# MCU.net
KiCad netlist of a schematic drawn in Altium Designer
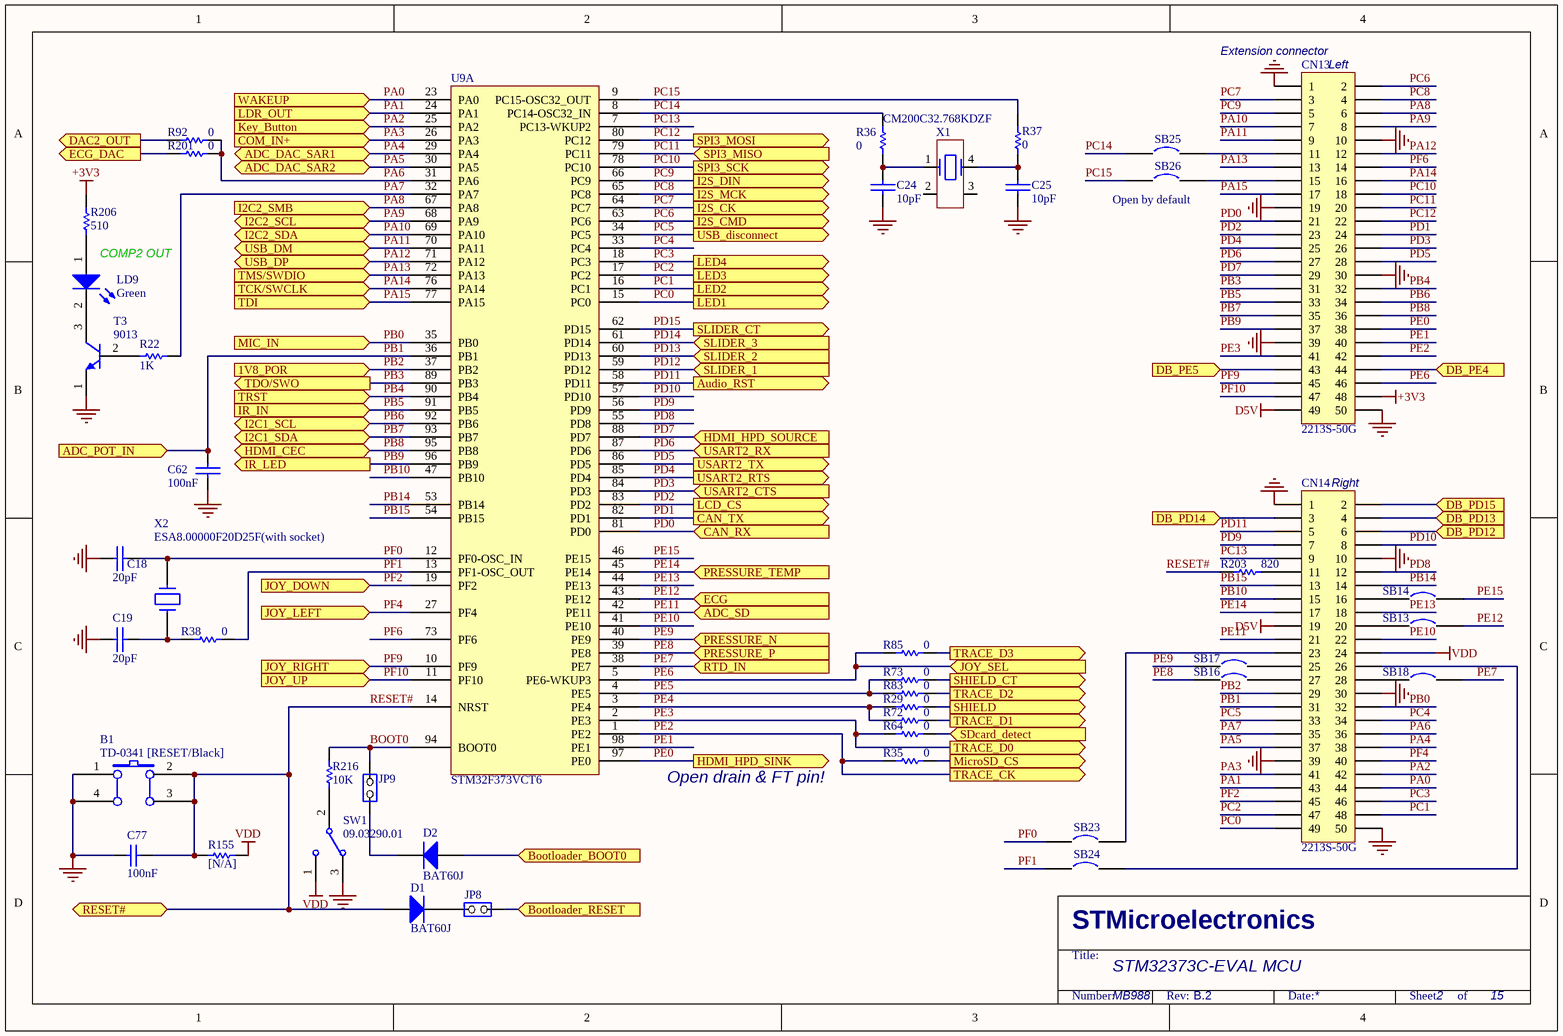
[diagram p0: MCU.SchDoc]

(export (version "E")
  (design (tool "Eeschema 10.0.6"))
  (components
    (comp (ref "B1")
      (value "TD-0341 [RESET/Black]")
      (footprint "PB10")
      (description "SE PUSHBUTTON")
      (libsource (lib "Documents") (part "SW PUSHBUTTON"))
    )
    (comp (ref "C18")
      (value "20pF")
      (footprint "0603C")
      (description "Capacitor")
      (libsource (lib "*") (part "CAP"))
    )
    (comp (ref "C19")
      (value "20pF")
      (footprint "0603C")
      (description "Capacitor")
      (libsource (lib "*") (part "CAP"))
    )
    (comp (ref "C24")
      (value "10pF")
      (footprint "0603C")
      (description "Capacitor")
      (libsource (lib "") (part "CAP_1"))
    )
    (comp (ref "C25")
      (value "10pF")
      (footprint "0603C")
      (description "Capacitor")
      (libsource (lib "") (part "CAP_1"))
    )
    (comp (ref "C62")
      (value "100nF")
      (footprint "0603C")
      (description "Capacitor")
      (libsource (lib "*") (part "CAP"))
    )
    (comp (ref "C77")
      (value "100nF")
      (footprint "0603C")
      (description "Capacitor")
      (fields (field (name "PUBLISHER") "Altium Limited"))
      (libsource (lib "Miscellaneous Devices") (part "CAP"))
    )
    (comp (ref "CN13")
      (value "2213S-50G")
      (footprint "2*25P")
      (description "Header, 25-Pin, Dual row")
      (fields (field (name "PUBLISHER") "Altium Limited"))
      (libsource (lib "Miscellaneous Connectors") (part "Header 25X2"))
    )
    (comp (ref "CN14")
      (value "2213S-50G")
      (footprint "2*25P")
      (description "Header, 25-Pin, Dual row")
      (fields (field (name "PUBLISHER") "Altium Limited"))
      (libsource (lib "Miscellaneous Connectors") (part "Header 25X2"))
    )
    (comp (ref "D1")
      (value "BAT60J")
      (footprint "SOD-323")
      (description "Default Diode")
      (fields (field (name "PUBLISHER") "Altium Limited"))
      (libsource (lib "Miscellaneous Devices") (part "Diode"))
    )
    (comp (ref "D2")
      (value "BAT60J")
      (footprint "SOD-323")
      (description "Default Diode")
      (fields (field (name "PUBLISHER") "Altium Limited"))
      (libsource (lib "Miscellaneous Devices") (part "Diode"))
    )
    (comp (ref "JP8") (value "~") (footprint "SIP2") (libsource (lib "*") (part "JP2")))
    (comp (ref "JP9") (value "~") (footprint "SIP2") (libsource (lib "*") (part "JP2")))
    (comp (ref "LD9")
      (value "Green")
      (footprint "0603D")
      (description "Typical RED, GREEN, YELLOW, AMBER GaAs LED")
      (fields (field (name "PUBLISHER") "Altium Limited"))
      (libsource (lib "Miscellaneous Devices") (part "LED2"))
    )
    (comp (ref "R22")
      (value "1K")
      (footprint "0603R")
      (description "Resistor")
      (fields (field (name "PUBLISHER") "Altium Limited"))
      (libsource (lib "Miscellaneous Devices") (part "Res1"))
    )
    (comp (ref "R29")
      (value "0")
      (footprint "0603R")
      (description "Resistor")
      (fields (field (name "PUBLISHER") "Altium Limited"))
      (libsource (lib "Miscellaneous Devices") (part "Res1"))
    )
    (comp (ref "R35")
      (value "0")
      (footprint "0603R")
      (description "Resistor")
      (fields (field (name "PUBLISHER") "Altium Limited"))
      (libsource (lib "Miscellaneous Devices") (part "Res1"))
    )
    (comp (ref "R36")
      (value "0")
      (footprint "0603R")
      (description "Resistor")
      (fields (field (name "PUBLISHER") "Altium Limited"))
      (libsource (lib "Miscellaneous Devices") (part "Res1"))
    )
    (comp (ref "R37")
      (value "0")
      (footprint "0603R")
      (description "Resistor")
      (fields (field (name "PUBLISHER") "Altium Limited"))
      (libsource (lib "Miscellaneous Devices") (part "Res1"))
    )
    (comp (ref "R38")
      (value "0")
      (footprint "0603R")
      (description "Resistor")
      (fields (field (name "PUBLISHER") "Altium Limited"))
      (libsource (lib "Miscellaneous Devices") (part "Res1"))
    )
    (comp (ref "R64")
      (value "0")
      (footprint "0603R")
      (description "Resistor")
      (fields (field (name "PUBLISHER") "Altium Limited"))
      (libsource (lib "Miscellaneous Devices") (part "Res1"))
    )
    (comp (ref "R72")
      (value "0")
      (footprint "0603R")
      (description "Resistor")
      (fields (field (name "PUBLISHER") "Altium Limited"))
      (libsource (lib "Miscellaneous Devices") (part "Res1"))
    )
    (comp (ref "R73")
      (value "0")
      (footprint "0603R")
      (description "Resistor")
      (fields (field (name "PUBLISHER") "Altium Limited"))
      (libsource (lib "Miscellaneous Devices") (part "Res1"))
    )
    (comp (ref "R83")
      (value "0")
      (footprint "0603R")
      (description "Resistor")
      (fields (field (name "PUBLISHER") "Altium Limited"))
      (libsource (lib "Miscellaneous Devices") (part "Res1"))
    )
    (comp (ref "R85")
      (value "0")
      (footprint "0603R")
      (description "Resistor")
      (fields (field (name "PUBLISHER") "Altium Limited"))
      (libsource (lib "Miscellaneous Devices") (part "Res1"))
    )
    (comp (ref "R92")
      (value "0")
      (footprint "0603R")
      (description "Resistor")
      (fields (field (name "PUBLISHER") "Altium Limited"))
      (libsource (lib "Miscellaneous Devices") (part "Res1"))
    )
    (comp (ref "R155")
      (value "[N/A]")
      (footprint "0603R")
      (description "Resistor")
      (fields (field (name "PUBLISHER") "Altium Limited"))
      (libsource (lib "Miscellaneous Devices") (part "res1"))
    )
    (comp (ref "R201")
      (value "0")
      (footprint "0603R")
      (description "Resistor")
      (fields (field (name "PUBLISHER") "Altium Limited"))
      (libsource (lib "Miscellaneous Devices") (part "Res1"))
    )
    (comp (ref "R203")
      (value "820")
      (footprint "0603R")
      (description "Resistor")
      (fields (field (name "PUBLISHER") "Altium Limited"))
      (libsource (lib "Miscellaneous Devices") (part "Res1"))
    )
    (comp (ref "R206")
      (value "510")
      (footprint "0603R")
      (description "Resistor")
      (fields (field (name "PUBLISHER") "Altium Limited"))
      (libsource (lib "Miscellaneous Devices") (part "Res1"))
    )
    (comp (ref "R216")
      (value "10K")
      (footprint "0603R")
      (description "Resistor")
      (fields (field (name "PUBLISHER") "Altium Limited"))
      (libsource (lib "Miscellaneous Devices") (part "res1"))
    )
    (comp (ref "SB13")
      (value "~")
      (footprint "JP2_SMD")
      (description "Circuit Breaker")
      (fields (field (name "PUBLISHER") "Altium Limited"))
      (libsource (lib "Miscellaneous Devices") (part "Circuit Breaker"))
    )
    (comp (ref "SB14")
      (value "~")
      (footprint "JP2_SMD")
      (description "Circuit Breaker")
      (fields (field (name "PUBLISHER") "Altium Limited"))
      (libsource (lib "Miscellaneous Devices") (part "Circuit Breaker"))
    )
    (comp (ref "SB16")
      (value "~")
      (footprint "JP2_SMD")
      (description "Circuit Breaker")
      (fields (field (name "PUBLISHER") "Altium Limited"))
      (libsource (lib "Miscellaneous Devices") (part "Circuit Breaker"))
    )
    (comp (ref "SB17")
      (value "~")
      (footprint "JP2_SMD")
      (description "Circuit Breaker")
      (fields (field (name "PUBLISHER") "Altium Limited"))
      (libsource (lib "Miscellaneous Devices") (part "Circuit Breaker"))
    )
    (comp (ref "SB18")
      (value "~")
      (footprint "JP2_SMD")
      (description "Circuit Breaker")
      (fields (field (name "PUBLISHER") "Altium Limited"))
      (libsource (lib "Miscellaneous Devices") (part "Circuit Breaker"))
    )
    (comp (ref "SB23")
      (value "~")
      (footprint "JP2_SMD")
      (description "Circuit Breaker")
      (fields (field (name "PUBLISHER") "Altium Limited"))
      (libsource (lib "Miscellaneous Devices") (part "Circuit Breaker"))
    )
    (comp (ref "SB24")
      (value "~")
      (footprint "JP2_SMD")
      (description "Circuit Breaker")
      (fields (field (name "PUBLISHER") "Altium Limited"))
      (libsource (lib "Miscellaneous Devices") (part "Circuit Breaker"))
    )
    (comp (ref "SB25")
      (value "~")
      (footprint "JP2_SMD")
      (description "Circuit Breaker")
      (fields (field (name "PUBLISHER") "Altium Limited"))
      (libsource (lib "Miscellaneous Devices") (part "Circuit Breaker"))
    )
    (comp (ref "SB26")
      (value "~")
      (footprint "JP2_SMD")
      (description "Circuit Breaker")
      (fields (field (name "PUBLISHER") "Altium Limited"))
      (libsource (lib "Miscellaneous Devices") (part "Circuit Breaker"))
    )
    (comp (ref "SW1")
      (value "09.03290.01")
      (footprint "SIP3")
      (description "SPDT Subminiature Toggle Switch, Right Angle Mounting, Vertical Actuation")
      (fields (field (name "PUBLISHER") "Altium Limited"))
      (libsource (lib "Miscellaneous Devices") (part "SW-SPDT"))
    )
    (comp (ref "T3")
      (value "9013")
      (footprint "SOT-23")
      (description "NPN Bipolar Transistor")
      (fields (field (name "PUBLISHER") "Altium Limited"))
      (libsource (lib "Miscellaneous Devices") (part "NPN"))
    )
    (comp (ref "U9")
      (value "STM32F373VCT6")
      (footprint "IC149-100-025-B5")
      (libsource (lib "MB988") (part "Goldfish"))
    )
    (comp (ref "X1") (value "CM200C32.768KDZF") (footprint "SM8") (libsource (lib "*") (part "MC306")))
    (comp (ref "X2")
      (value "ESA8.00000F20D25F(with socket)")
      (footprint "XTAL_socket")
      (description "Crystal")
      (libsource (lib "*") (part "CRYSTAL"))
    )
  )
  (nets
    (net (code "1") (name "+3V3") (class "Default")
      (node (ref "CN13") (pin "48") (pinfunction "48_48") (pintype "passive"))
      (node (ref "R206") (pin "1") (pinfunction "1_1") (pintype "passive"))
    )
    (net (code "2") (name "/BOOT0") (class "Default")
      (node (ref "JP9") (pin "2") (pinfunction "NO_2") (pintype "passive"))
      (node (ref "R216") (pin "1") (pinfunction "1_1") (pintype "passive"))
      (node (ref "U9") (pin "94") (pinfunction "BOOT0_94") (pintype "passive"))
    )
    (net (code "3") (name "/Bootloader_BOOT0") (class "Default")
      (node (ref "D2") (pin "1") (pinfunction "A_1") (pintype "passive"))
    )
    (net (code "4") (name "/Bootloader_RESET") (class "Default")
      (node (ref "JP8") (pin "2") (pinfunction "NO_2") (pintype "passive"))
    )
    (net (code "5") (name "/DAC2_OUT") (class "Default")
      (node (ref "R92") (pin "2") (pinfunction "2_2") (pintype "passive"))
    )
    (net (code "6") (name "/DB_PD12") (class "Default")
      (node (ref "CN14") (pin "6") (pinfunction "6_6") (pintype "passive"))
    )
    (net (code "7") (name "/DB_PD13") (class "Default")
      (node (ref "CN14") (pin "4") (pinfunction "4_4") (pintype "passive"))
    )
    (net (code "8") (name "/DB_PD14") (class "Default")
      (node (ref "CN14") (pin "3") (pinfunction "3_3") (pintype "passive"))
    )
    (net (code "9") (name "/DB_PD15") (class "Default")
      (node (ref "CN14") (pin "2") (pinfunction "2_2") (pintype "passive"))
    )
    (net (code "10") (name "/DB_PE4") (class "Default")
      (node (ref "CN13") (pin "44") (pinfunction "44_44") (pintype "passive"))
    )
    (net (code "11") (name "/DB_PE5") (class "Default")
      (node (ref "CN13") (pin "43") (pinfunction "43_43") (pintype "passive"))
    )
    (net (code "12") (name "/ECG_DAC") (class "Default")
      (node (ref "R201") (pin "2") (pinfunction "2_2") (pintype "passive"))
    )
    (net (code "13") (name "/MicroSD_CS") (class "Default")
      (node (ref "R35") (pin "1") (pinfunction "1_1") (pintype "passive"))
    )
    (net (code "14") (name "/PA0") (class "Default")
      (node (ref "CN14") (pin "44") (pinfunction "44_44") (pintype "passive"))
      (node (ref "U9") (pin "23") (pinfunction "PA0_23") (pintype "passive"))
    )
    (net (code "15") (name "/PA1") (class "Default")
      (node (ref "CN14") (pin "43") (pinfunction "43_43") (pintype "passive"))
      (node (ref "U9") (pin "24") (pinfunction "PA1_24") (pintype "passive"))
    )
    (net (code "16") (name "/PA2") (class "Default")
      (node (ref "CN14") (pin "42") (pinfunction "42_42") (pintype "passive"))
      (node (ref "U9") (pin "25") (pinfunction "PA2_25") (pintype "passive"))
    )
    (net (code "17") (name "/PA3") (class "Default")
      (node (ref "CN14") (pin "41") (pinfunction "41_41") (pintype "passive"))
      (node (ref "U9") (pin "26") (pinfunction "PA3_26") (pintype "passive"))
    )
    (net (code "18") (name "/PA4") (class "Default")
      (node (ref "CN14") (pin "38") (pinfunction "38_38") (pintype "passive"))
      (node (ref "U9") (pin "29") (pinfunction "PA4_29") (pintype "passive"))
    )
    (net (code "19") (name "/PA5") (class "Default")
      (node (ref "CN14") (pin "37") (pinfunction "37_37") (pintype "passive"))
      (node (ref "U9") (pin "30") (pinfunction "PA5_30") (pintype "passive"))
    )
    (net (code "20") (name "/PA6") (class "Default")
      (node (ref "CN14") (pin "36") (pinfunction "36_36") (pintype "passive"))
      (node (ref "R201") (pin "1") (pinfunction "1_1") (pintype "passive"))
      (node (ref "R92") (pin "1") (pinfunction "1_1") (pintype "passive"))
      (node (ref "U9") (pin "31") (pinfunction "PA6_31") (pintype "passive"))
    )
    (net (code "21") (name "/PA7") (class "Default")
      (node (ref "CN14") (pin "35") (pinfunction "35_35") (pintype "passive"))
      (node (ref "R22") (pin "2") (pinfunction "2_2") (pintype "passive"))
      (node (ref "U9") (pin "32") (pinfunction "PA7_32") (pintype "passive"))
    )
    (net (code "22") (name "/PA8") (class "Default")
      (node (ref "CN13") (pin "6") (pinfunction "6_6") (pintype "passive"))
      (node (ref "U9") (pin "67") (pinfunction "PA8_67") (pintype "passive"))
    )
    (net (code "23") (name "/PA9") (class "Default")
      (node (ref "CN13") (pin "8") (pinfunction "8_8") (pintype "passive"))
      (node (ref "U9") (pin "68") (pinfunction "PA9_68") (pintype "passive"))
    )
    (net (code "24") (name "/PA10") (class "Default")
      (node (ref "CN13") (pin "7") (pinfunction "7_7") (pintype "passive"))
      (node (ref "U9") (pin "69") (pinfunction "PA10_69") (pintype "passive"))
    )
    (net (code "25") (name "/PA11") (class "Default")
      (node (ref "CN13") (pin "9") (pinfunction "9_9") (pintype "passive"))
      (node (ref "U9") (pin "70") (pinfunction "PA11_70") (pintype "passive"))
    )
    (net (code "26") (name "/PA12") (class "Default")
      (node (ref "CN13") (pin "12") (pinfunction "12_12") (pintype "passive"))
      (node (ref "U9") (pin "71") (pinfunction "PA12_71") (pintype "passive"))
    )
    (net (code "27") (name "/PA13") (class "Default")
      (node (ref "CN13") (pin "13") (pinfunction "13_13") (pintype "passive"))
      (node (ref "U9") (pin "72") (pinfunction "PA13_72") (pintype "passive"))
    )
    (net (code "28") (name "/PA14") (class "Default")
      (node (ref "CN13") (pin "16") (pinfunction "16_16") (pintype "passive"))
      (node (ref "U9") (pin "76") (pinfunction "PA14_76") (pintype "passive"))
    )
    (net (code "29") (name "/PA15") (class "Default")
      (node (ref "CN13") (pin "17") (pinfunction "17_17") (pintype "passive"))
      (node (ref "U9") (pin "77") (pinfunction "PA15_77") (pintype "passive"))
    )
    (net (code "30") (name "/PB0") (class "Default")
      (node (ref "CN14") (pin "32") (pinfunction "32_32") (pintype "passive"))
      (node (ref "U9") (pin "35") (pinfunction "PB0_35") (pintype "passive"))
    )
    (net (code "31") (name "/PB1") (class "Default")
      (node (ref "C62") (pin "2") (pinfunction "2_2") (pintype "passive"))
      (node (ref "CN14") (pin "31") (pinfunction "31_31") (pintype "passive"))
      (node (ref "U9") (pin "36") (pinfunction "PB1_36") (pintype "passive"))
    )
    (net (code "32") (name "/PB2") (class "Default")
      (node (ref "CN14") (pin "29") (pinfunction "29_29") (pintype "passive"))
      (node (ref "U9") (pin "37") (pinfunction "PB2_37") (pintype "passive"))
    )
    (net (code "33") (name "/PB3") (class "Default")
      (node (ref "CN13") (pin "31") (pinfunction "31_31") (pintype "passive"))
      (node (ref "U9") (pin "89") (pinfunction "PB3_89") (pintype "passive"))
    )
    (net (code "34") (name "/PB4") (class "Default")
      (node (ref "CN13") (pin "32") (pinfunction "32_32") (pintype "passive"))
      (node (ref "U9") (pin "90") (pinfunction "PB4_90") (pintype "passive"))
    )
    (net (code "35") (name "/PB5") (class "Default")
      (node (ref "CN13") (pin "33") (pinfunction "33_33") (pintype "passive"))
      (node (ref "U9") (pin "91") (pinfunction "PB5_91") (pintype "passive"))
    )
    (net (code "36") (name "/PB6") (class "Default")
      (node (ref "CN13") (pin "34") (pinfunction "34_34") (pintype "passive"))
      (node (ref "U9") (pin "92") (pinfunction "PB6_92") (pintype "passive"))
    )
    (net (code "37") (name "/PB7") (class "Default")
      (node (ref "CN13") (pin "35") (pinfunction "35_35") (pintype "passive"))
      (node (ref "U9") (pin "93") (pinfunction "PB7_93") (pintype "passive"))
    )
    (net (code "38") (name "/PB8") (class "Default")
      (node (ref "CN13") (pin "36") (pinfunction "36_36") (pintype "passive"))
      (node (ref "U9") (pin "95") (pinfunction "PB8_95") (pintype "passive"))
    )
    (net (code "39") (name "/PB9") (class "Default")
      (node (ref "CN13") (pin "37") (pinfunction "37_37") (pintype "passive"))
      (node (ref "U9") (pin "96") (pinfunction "PB9_96") (pintype "passive"))
    )
    (net (code "40") (name "/PB10") (class "Default")
      (node (ref "CN14") (pin "15") (pinfunction "15_15") (pintype "passive"))
      (node (ref "U9") (pin "47") (pinfunction "PB10_47") (pintype "passive"))
    )
    (net (code "41") (name "/PB14") (class "Default")
      (node (ref "CN14") (pin "14") (pinfunction "14_14") (pintype "passive"))
      (node (ref "U9") (pin "53") (pinfunction "PB14_53") (pintype "passive"))
    )
    (net (code "42") (name "/PB15") (class "Default")
      (node (ref "CN14") (pin "13") (pinfunction "13_13") (pintype "passive"))
      (node (ref "U9") (pin "54") (pinfunction "PB15_54") (pintype "passive"))
    )
    (net (code "43") (name "/PC0") (class "Default")
      (node (ref "CN14") (pin "49") (pinfunction "49_49") (pintype "passive"))
      (node (ref "U9") (pin "15") (pinfunction "PC0_15") (pintype "passive"))
    )
    (net (code "44") (name "/PC1") (class "Default")
      (node (ref "CN14") (pin "48") (pinfunction "48_48") (pintype "passive"))
      (node (ref "U9") (pin "16") (pinfunction "PC1_16") (pintype "passive"))
    )
    (net (code "45") (name "/PC2") (class "Default")
      (node (ref "CN14") (pin "47") (pinfunction "47_47") (pintype "passive"))
      (node (ref "U9") (pin "17") (pinfunction "PC2_17") (pintype "passive"))
    )
    (net (code "46") (name "/PC3") (class "Default")
      (node (ref "CN14") (pin "46") (pinfunction "46_46") (pintype "passive"))
      (node (ref "U9") (pin "18") (pinfunction "PC3_18") (pintype "passive"))
    )
    (net (code "47") (name "/PC4") (class "Default")
      (node (ref "CN14") (pin "34") (pinfunction "34_34") (pintype "passive"))
      (node (ref "U9") (pin "33") (pinfunction "PC4_33") (pintype "passive"))
    )
    (net (code "48") (name "/PC5") (class "Default")
      (node (ref "CN14") (pin "33") (pinfunction "33_33") (pintype "passive"))
      (node (ref "U9") (pin "34") (pinfunction "PC5_34") (pintype "passive"))
    )
    (net (code "49") (name "/PC6") (class "Default")
      (node (ref "CN13") (pin "2") (pinfunction "2_2") (pintype "passive"))
      (node (ref "U9") (pin "63") (pinfunction "PC6_63") (pintype "passive"))
    )
    (net (code "50") (name "/PC7") (class "Default")
      (node (ref "CN13") (pin "3") (pinfunction "3_3") (pintype "passive"))
      (node (ref "U9") (pin "64") (pinfunction "PC7_64") (pintype "passive"))
    )
    (net (code "51") (name "/PC8") (class "Default")
      (node (ref "CN13") (pin "4") (pinfunction "4_4") (pintype "passive"))
      (node (ref "U9") (pin "65") (pinfunction "PC8_65") (pintype "passive"))
    )
    (net (code "52") (name "/PC9") (class "Default")
      (node (ref "CN13") (pin "5") (pinfunction "5_5") (pintype "passive"))
      (node (ref "U9") (pin "66") (pinfunction "PC9_66") (pintype "passive"))
    )
    (net (code "53") (name "/PC10") (class "Default")
      (node (ref "CN13") (pin "18") (pinfunction "18_18") (pintype "passive"))
      (node (ref "U9") (pin "78") (pinfunction "PC10_78") (pintype "passive"))
    )
    (net (code "54") (name "/PC11") (class "Default")
      (node (ref "CN13") (pin "20") (pinfunction "20_20") (pintype "passive"))
      (node (ref "U9") (pin "79") (pinfunction "PC11_79") (pintype "passive"))
    )
    (net (code "55") (name "/PC12") (class "Default")
      (node (ref "CN13") (pin "22") (pinfunction "22_22") (pintype "passive"))
      (node (ref "U9") (pin "80") (pinfunction "PC12_80") (pintype "passive"))
    )
    (net (code "56") (name "/PC13") (class "Default")
      (node (ref "CN14") (pin "9") (pinfunction "9_9") (pintype "passive"))
      (node (ref "U9") (pin "7") (pinfunction "PC13-WKUP2_7") (pintype "passive"))
    )
    (net (code "57") (name "/PC14") (class "Default")
      (node (ref "R36") (pin "2") (pinfunction "2_2") (pintype "passive"))
      (node (ref "SB25") (pin "1") (pinfunction "1_1") (pintype "passive"))
      (node (ref "U9") (pin "8") (pinfunction "PC14-OSC32_IN_8") (pintype "passive"))
    )
    (net (code "58") (name "/PC15") (class "Default")
      (node (ref "R37") (pin "2") (pinfunction "2_2") (pintype "passive"))
      (node (ref "SB26") (pin "1") (pinfunction "1_1") (pintype "passive"))
      (node (ref "U9") (pin "9") (pinfunction "PC15-OSC32_OUT_9") (pintype "passive"))
    )
    (net (code "59") (name "/PD0") (class "Default")
      (node (ref "CN13") (pin "21") (pinfunction "21_21") (pintype "passive"))
      (node (ref "U9") (pin "81") (pinfunction "PD0_81") (pintype "passive"))
    )
    (net (code "60") (name "/PD1") (class "Default")
      (node (ref "CN13") (pin "24") (pinfunction "24_24") (pintype "passive"))
      (node (ref "U9") (pin "82") (pinfunction "PD1_82") (pintype "passive"))
    )
    (net (code "61") (name "/PD2") (class "Default")
      (node (ref "CN13") (pin "23") (pinfunction "23_23") (pintype "passive"))
      (node (ref "U9") (pin "83") (pinfunction "PD2_83") (pintype "passive"))
    )
    (net (code "62") (name "/PD3") (class "Default")
      (node (ref "CN13") (pin "26") (pinfunction "26_26") (pintype "passive"))
      (node (ref "U9") (pin "84") (pinfunction "PD3_84") (pintype "passive"))
    )
    (net (code "63") (name "/PD4") (class "Default")
      (node (ref "CN13") (pin "25") (pinfunction "25_25") (pintype "passive"))
      (node (ref "U9") (pin "85") (pinfunction "PD4_85") (pintype "passive"))
    )
    (net (code "64") (name "/PD5") (class "Default")
      (node (ref "CN13") (pin "28") (pinfunction "28_28") (pintype "passive"))
      (node (ref "U9") (pin "86") (pinfunction "PD5_86") (pintype "passive"))
    )
    (net (code "65") (name "/PD6") (class "Default")
      (node (ref "CN13") (pin "27") (pinfunction "27_27") (pintype "passive"))
      (node (ref "U9") (pin "87") (pinfunction "PD6_87") (pintype "passive"))
    )
    (net (code "66") (name "/PD7") (class "Default")
      (node (ref "CN13") (pin "29") (pinfunction "29_29") (pintype "passive"))
      (node (ref "U9") (pin "88") (pinfunction "PD7_88") (pintype "passive"))
    )
    (net (code "67") (name "/PD8") (class "Default")
      (node (ref "CN14") (pin "12") (pinfunction "12_12") (pintype "passive"))
      (node (ref "U9") (pin "55") (pinfunction "PD8_55") (pintype "passive"))
    )
    (net (code "68") (name "/PD9") (class "Default")
      (node (ref "CN14") (pin "7") (pinfunction "7_7") (pintype "passive"))
      (node (ref "U9") (pin "56") (pinfunction "PD9_56") (pintype "passive"))
    )
    (net (code "69") (name "/PD10") (class "Default")
      (node (ref "CN14") (pin "8") (pinfunction "8_8") (pintype "passive"))
      (node (ref "U9") (pin "57") (pinfunction "PD10_57") (pintype "passive"))
    )
    (net (code "70") (name "/PD11") (class "Default")
      (node (ref "CN14") (pin "5") (pinfunction "5_5") (pintype "passive"))
      (node (ref "U9") (pin "58") (pinfunction "PD11_58") (pintype "passive"))
    )
    (net (code "71") (name "/PD12") (class "Default")
      (node (ref "U9") (pin "59") (pinfunction "PD12_59") (pintype "passive"))
    )
    (net (code "72") (name "/PD13") (class "Default")
      (node (ref "U9") (pin "60") (pinfunction "PD13_60") (pintype "passive"))
    )
    (net (code "73") (name "/PD14") (class "Default")
      (node (ref "U9") (pin "61") (pinfunction "PD14_61") (pintype "passive"))
    )
    (net (code "74") (name "/PD15") (class "Default")
      (node (ref "U9") (pin "62") (pinfunction "PD15_62") (pintype "passive"))
    )
    (net (code "75") (name "/PE0") (class "Default")
      (node (ref "CN13") (pin "38") (pinfunction "38_38") (pintype "passive"))
      (node (ref "U9") (pin "97") (pinfunction "PE0_97") (pintype "passive"))
    )
    (net (code "76") (name "/PE1") (class "Default")
      (node (ref "CN13") (pin "40") (pinfunction "40_40") (pintype "passive"))
      (node (ref "U9") (pin "98") (pinfunction "PE1_98") (pintype "passive"))
    )
    (net (code "77") (name "/PE2") (class "Default")
      (node (ref "CN13") (pin "42") (pinfunction "42_42") (pintype "passive"))
      (node (ref "R35") (pin "2") (pinfunction "2_2") (pintype "passive"))
      (node (ref "U9") (pin "1") (pinfunction "PE2_1") (pintype "passive"))
    )
    (net (code "78") (name "/PE3") (class "Default")
      (node (ref "CN13") (pin "41") (pinfunction "41_41") (pintype "passive"))
      (node (ref "R64") (pin "2") (pinfunction "2_2") (pintype "passive"))
      (node (ref "U9") (pin "2") (pinfunction "PE3_2") (pintype "passive"))
    )
    (net (code "79") (name "/PE4") (class "Default")
      (node (ref "R29") (pin "2") (pinfunction "2_2") (pintype "passive"))
      (node (ref "R72") (pin "2") (pinfunction "2_2") (pintype "passive"))
      (node (ref "U9") (pin "3") (pinfunction "PE4_3") (pintype "passive"))
    )
    (net (code "80") (name "/PE5") (class "Default")
      (node (ref "R73") (pin "2") (pinfunction "2_2") (pintype "passive"))
      (node (ref "R83") (pin "2") (pinfunction "2_2") (pintype "passive"))
      (node (ref "U9") (pin "4") (pinfunction "PE5_4") (pintype "passive"))
    )
    (net (code "81") (name "/PE6") (class "Default")
      (node (ref "CN13") (pin "46") (pinfunction "46_46") (pintype "passive"))
      (node (ref "R85") (pin "2") (pinfunction "2_2") (pintype "passive"))
      (node (ref "U9") (pin "5") (pinfunction "PE6-WKUP3_5") (pintype "passive"))
    )
    (net (code "82") (name "/PE7") (class "Default")
      (node (ref "SB18") (pin "2") (pinfunction "2_2") (pintype "passive"))
      (node (ref "U9") (pin "38") (pinfunction "PE7_38") (pintype "passive"))
    )
    (net (code "83") (name "/PE8") (class "Default")
      (node (ref "SB16") (pin "1") (pinfunction "1_1") (pintype "passive"))
      (node (ref "U9") (pin "39") (pinfunction "PE8_39") (pintype "passive"))
    )
    (net (code "84") (name "/PE9") (class "Default")
      (node (ref "SB17") (pin "1") (pinfunction "1_1") (pintype "passive"))
      (node (ref "U9") (pin "40") (pinfunction "PE9_40") (pintype "passive"))
    )
    (net (code "85") (name "/PE10") (class "Default")
      (node (ref "CN14") (pin "22") (pinfunction "22_22") (pintype "passive"))
      (node (ref "U9") (pin "41") (pinfunction "PE10_41") (pintype "passive"))
    )
    (net (code "86") (name "/PE11") (class "Default")
      (node (ref "CN14") (pin "21") (pinfunction "21_21") (pintype "passive"))
      (node (ref "U9") (pin "42") (pinfunction "PE11_42") (pintype "passive"))
    )
    (net (code "87") (name "/PE12") (class "Default")
      (node (ref "SB13") (pin "2") (pinfunction "2_2") (pintype "passive"))
      (node (ref "U9") (pin "43") (pinfunction "PE12_43") (pintype "passive"))
    )
    (net (code "88") (name "/PE13") (class "Default")
      (node (ref "CN14") (pin "18") (pinfunction "18_18") (pintype "passive"))
      (node (ref "U9") (pin "44") (pinfunction "PE13_44") (pintype "passive"))
    )
    (net (code "89") (name "/PE14") (class "Default")
      (node (ref "CN14") (pin "17") (pinfunction "17_17") (pintype "passive"))
      (node (ref "U9") (pin "45") (pinfunction "PE14_45") (pintype "passive"))
    )
    (net (code "90") (name "/PE15") (class "Default")
      (node (ref "SB14") (pin "2") (pinfunction "2_2") (pintype "passive"))
      (node (ref "U9") (pin "46") (pinfunction "PE15_46") (pintype "passive"))
    )
    (net (code "91") (name "/PF0") (class "Default")
      (node (ref "C18") (pin "1") (pinfunction "1_1") (pintype "passive"))
      (node (ref "SB23") (pin "1") (pinfunction "1_1") (pintype "passive"))
      (node (ref "U9") (pin "12") (pinfunction "PF0-OSC_IN_12") (pintype "passive"))
      (node (ref "X2") (pin "2") (pinfunction "2_2") (pintype "passive"))
    )
    (net (code "92") (name "/PF1") (class "Default")
      (node (ref "R38") (pin "1") (pinfunction "1_1") (pintype "passive"))
      (node (ref "SB24") (pin "1") (pinfunction "1_1") (pintype "passive"))
      (node (ref "U9") (pin "13") (pinfunction "PF1-OSC_OUT_13") (pintype "passive"))
    )
    (net (code "93") (name "/PF2") (class "Default")
      (node (ref "CN14") (pin "45") (pinfunction "45_45") (pintype "passive"))
      (node (ref "U9") (pin "19") (pinfunction "PF2_19") (pintype "passive"))
    )
    (net (code "94") (name "/PF4") (class "Default")
      (node (ref "CN14") (pin "40") (pinfunction "40_40") (pintype "passive"))
      (node (ref "U9") (pin "27") (pinfunction "PF4_27") (pintype "passive"))
    )
    (net (code "95") (name "/PF6") (class "Default")
      (node (ref "CN13") (pin "14") (pinfunction "14_14") (pintype "passive"))
      (node (ref "U9") (pin "73") (pinfunction "PF6_73") (pintype "passive"))
    )
    (net (code "96") (name "/PF9") (class "Default")
      (node (ref "CN13") (pin "45") (pinfunction "45_45") (pintype "passive"))
      (node (ref "U9") (pin "10") (pinfunction "PF9_10") (pintype "passive"))
    )
    (net (code "97") (name "/PF10") (class "Default")
      (node (ref "CN13") (pin "47") (pinfunction "47_47") (pintype "passive"))
      (node (ref "U9") (pin "11") (pinfunction "PF10_11") (pintype "passive"))
    )
    (net (code "98") (name "/RESET#") (class "Default")
      (node (ref "B1") (pin "2") (pinfunction "B0_2") (pintype "passive"))
      (node (ref "B1") (pin "3") (pinfunction "B1_3") (pintype "passive"))
      (node (ref "C77") (pin "2") (pinfunction "2_2") (pintype "passive"))
      (node (ref "D1") (pin "1") (pinfunction "A_1") (pintype "passive"))
      (node (ref "R155") (pin "1") (pinfunction "1_1") (pintype "passive"))
      (node (ref "R203") (pin "2") (pinfunction "2_2") (pintype "passive"))
      (node (ref "U9") (pin "14") (pinfunction "NRST_14") (pintype "passive"))
    )
    (net (code "99") (name "/SDcard_detect") (class "Default")
      (node (ref "R64") (pin "1") (pinfunction "1_1") (pintype "passive"))
    )
    (net (code "100") (name "/SHIELD") (class "Default")
      (node (ref "R29") (pin "1") (pinfunction "1_1") (pintype "passive"))
    )
    (net (code "101") (name "/SHIELD_CT") (class "Default")
      (node (ref "R73") (pin "1") (pinfunction "1_1") (pintype "passive"))
    )
    (net (code "102") (name "/TRACE_D1") (class "Default")
      (node (ref "R72") (pin "1") (pinfunction "1_1") (pintype "passive"))
    )
    (net (code "103") (name "/TRACE_D2") (class "Default")
      (node (ref "R83") (pin "1") (pinfunction "1_1") (pintype "passive"))
    )
    (net (code "104") (name "/TRACE_D3") (class "Default")
      (node (ref "R85") (pin "1") (pinfunction "1_1") (pintype "passive"))
    )
    (net (code "105") (name "D5V") (class "Default")
      (node (ref "CN13") (pin "49") (pinfunction "49_49") (pintype "passive"))
      (node (ref "CN14") (pin "19") (pinfunction "19_19") (pintype "passive"))
    )
    (net (code "106") (name "GND") (class "Default")
      (node (ref "B1") (pin "1") (pinfunction "A0_1") (pintype "passive"))
      (node (ref "B1") (pin "4") (pinfunction "A1_4") (pintype "passive"))
      (node (ref "C18") (pin "2") (pinfunction "2_2") (pintype "passive"))
      (node (ref "C19") (pin "2") (pinfunction "2_2") (pintype "passive"))
      (node (ref "C24") (pin "2") (pinfunction "2_2") (pintype "passive"))
      (node (ref "C25") (pin "2") (pinfunction "2_2") (pintype "passive"))
      (node (ref "C62") (pin "1") (pinfunction "1_1") (pintype "passive"))
      (node (ref "C77") (pin "1") (pinfunction "1_1") (pintype "passive"))
      (node (ref "CN13") (pin "1") (pinfunction "1_1") (pintype "passive"))
      (node (ref "CN13") (pin "10") (pinfunction "10_10") (pintype "passive"))
      (node (ref "CN13") (pin "19") (pinfunction "19_19") (pintype "passive"))
      (node (ref "CN13") (pin "30") (pinfunction "30_30") (pintype "passive"))
      (node (ref "CN13") (pin "39") (pinfunction "39_39") (pintype "passive"))
      (node (ref "CN13") (pin "50") (pinfunction "50_50") (pintype "passive"))
      (node (ref "CN14") (pin "1") (pinfunction "1_1") (pintype "passive"))
      (node (ref "CN14") (pin "10") (pinfunction "10_10") (pintype "passive"))
      (node (ref "CN14") (pin "30") (pinfunction "30_30") (pintype "passive"))
      (node (ref "CN14") (pin "39") (pinfunction "39_39") (pintype "passive"))
      (node (ref "CN14") (pin "50") (pinfunction "50_50") (pintype "passive"))
      (node (ref "SW1") (pin "3") (pintype "passive"))
      (node (ref "T3") (pin "1") (pinfunction "E_1") (pintype "passive"))
    )
    (net (code "107") (name "Net-(C19-Pad1)") (class "Default")
      (node (ref "C19") (pin "1") (pinfunction "1_1") (pintype "passive"))
      (node (ref "R38") (pin "2") (pinfunction "2_2") (pintype "passive"))
      (node (ref "X2") (pin "1") (pinfunction "1_1") (pintype "passive"))
    )
    (net (code "108") (name "Net-(C24-Pad1)") (class "Default")
      (node (ref "C24") (pin "1") (pinfunction "1_1") (pintype "passive"))
      (node (ref "R36") (pin "1") (pinfunction "1_1") (pintype "passive"))
      (node (ref "X1") (pin "1") (pinfunction "1_1") (pintype "passive"))
    )
    (net (code "109") (name "Net-(C25-Pad1)") (class "Default")
      (node (ref "C25") (pin "1") (pinfunction "1_1") (pintype "passive"))
      (node (ref "R37") (pin "1") (pinfunction "1_1") (pintype "passive"))
      (node (ref "X1") (pin "4") (pinfunction "4_4") (pintype "passive"))
    )
    (net (code "110") (name "Net-(CN13-Pad11)") (class "Default")
      (node (ref "CN13") (pin "11") (pinfunction "11_11") (pintype "passive"))
      (node (ref "SB25") (pin "2") (pinfunction "2_2") (pintype "passive"))
    )
    (net (code "111") (name "Net-(CN13-Pad15)") (class "Default")
      (node (ref "CN13") (pin "15") (pinfunction "15_15") (pintype "passive"))
      (node (ref "SB26") (pin "2") (pinfunction "2_2") (pintype "passive"))
    )
    (net (code "112") (name "Net-(CN14-Pad11)") (class "Default")
      (node (ref "CN14") (pin "11") (pinfunction "11_11") (pintype "passive"))
      (node (ref "R203") (pin "1") (pinfunction "1_1") (pintype "passive"))
    )
    (net (code "113") (name "Net-(CN14-Pad16)") (class "Default")
      (node (ref "CN14") (pin "16") (pinfunction "16_16") (pintype "passive"))
      (node (ref "SB14") (pin "1") (pinfunction "1_1") (pintype "passive"))
    )
    (net (code "114") (name "Net-(CN14-Pad20)") (class "Default")
      (node (ref "CN14") (pin "20") (pinfunction "20_20") (pintype "passive"))
      (node (ref "SB13") (pin "1") (pinfunction "1_1") (pintype "passive"))
    )
    (net (code "115") (name "Net-(CN14-Pad23)") (class "Default")
      (node (ref "CN14") (pin "23") (pinfunction "23_23") (pintype "passive"))
      (node (ref "SB23") (pin "2") (pinfunction "2_2") (pintype "passive"))
    )
    (net (code "116") (name "Net-(CN14-Pad25)") (class "Default")
      (node (ref "CN14") (pin "25") (pinfunction "25_25") (pintype "passive"))
      (node (ref "SB17") (pin "2") (pinfunction "2_2") (pintype "passive"))
    )
    (net (code "117") (name "Net-(CN14-Pad26)") (class "Default")
      (node (ref "CN14") (pin "26") (pinfunction "26_26") (pintype "passive"))
      (node (ref "SB24") (pin "2") (pinfunction "2_2") (pintype "passive"))
    )
    (net (code "118") (name "Net-(CN14-Pad27)") (class "Default")
      (node (ref "CN14") (pin "27") (pinfunction "27_27") (pintype "passive"))
      (node (ref "SB16") (pin "2") (pinfunction "2_2") (pintype "passive"))
    )
    (net (code "119") (name "Net-(CN14-Pad28)") (class "Default")
      (node (ref "CN14") (pin "28") (pinfunction "28_28") (pintype "passive"))
      (node (ref "SB18") (pin "1") (pinfunction "1_1") (pintype "passive"))
    )
    (net (code "120") (name "Net-(D1-K)") (class "Default")
      (node (ref "D1") (pin "2") (pinfunction "K_2") (pintype "passive"))
      (node (ref "JP8") (pin "1") (pinfunction "COMMON_1") (pintype "passive"))
    )
    (net (code "121") (name "Net-(D2-K)") (class "Default")
      (node (ref "D2") (pin "2") (pinfunction "K_2") (pintype "passive"))
      (node (ref "JP9") (pin "1") (pinfunction "COMMON_1") (pintype "passive"))
    )
    (net (code "122") (name "Net-(LD9-A)") (class "Default")
      (node (ref "LD9") (pin "1") (pinfunction "A_1") (pintype "passive"))
      (node (ref "R206") (pin "2") (pinfunction "2_2") (pintype "passive"))
    )
    (net (code "123") (name "Net-(LD9-K)") (class "Default")
      (node (ref "LD9") (pin "2") (pinfunction "K_2") (pintype "passive"))
      (node (ref "T3") (pin "3") (pinfunction "C_3") (pintype "passive"))
    )
    (net (code "124") (name "Net-(R216-Pad2)") (class "Default")
      (node (ref "R216") (pin "2") (pinfunction "2_2") (pintype "passive"))
      (node (ref "SW1") (pin "2") (pintype "passive"))
    )
    (net (code "125") (name "Net-(T3-B)") (class "Default")
      (node (ref "R22") (pin "1") (pinfunction "1_1") (pintype "passive"))
      (node (ref "T3") (pin "2") (pinfunction "B_2") (pintype "passive"))
    )
    (net (code "126") (name "VDD") (class "Default")
      (node (ref "CN14") (pin "24") (pinfunction "24_24") (pintype "passive"))
      (node (ref "R155") (pin "2") (pinfunction "2_2") (pintype "passive"))
      (node (ref "SW1") (pin "1") (pintype "passive"))
    )
    (net (code "127") (name "unconnected-(X1-Pad2)") (class "Default")
      (node (ref "X1") (pin "2") (pinfunction "2_2") (pintype "passive"))
    )
    (net (code "128") (name "unconnected-(X1-Pad3)") (class "Default")
      (node (ref "X1") (pin "3") (pinfunction "3_3") (pintype "passive"))
    )
  )
)
